# ders1.net
KiCad netlist of a schematic drawn in EAGLE
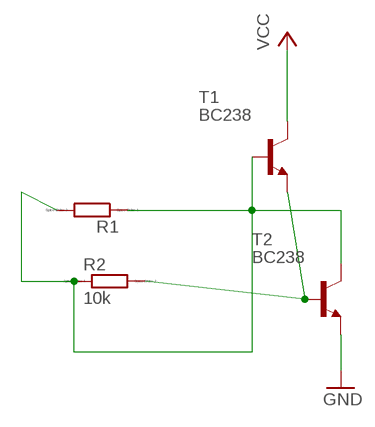
[diagram p0: schematic, sheet 1]

(export (version "E")
  (design (tool "Eeschema 10.0.6"))
  (components
    (comp (ref "R1") (value "R") (footprint "eagle-import:R0805") (libsource (lib "eagle-import") (part "R")))
    (comp (ref "R2")
      (value "10k")
      (footprint "eagle-import:R0805")
      (libsource (lib "eagle-import") (part "R"))
    )
    (comp (ref "T1")
      (value "BC238")
      (footprint "eagle-import:TO92")
      (libsource (lib "eagle-import") (part "BC238"))
    )
    (comp (ref "T2")
      (value "BC238")
      (footprint "eagle-import:TO92")
      (libsource (lib "eagle-import") (part "BC238"))
    )
  )
  (nets
    (net (code "1") (name "GND") (class "Default")
      (node (ref "T2") (pin "1") (pinfunction "E_1") (pintype "passive"))
    )
    (net (code "2") (name "Net-(T1-B)") (class "Default")
      (node (ref "R1") (pin "1") (pinfunction "1_1") (pintype "passive"))
      (node (ref "R1") (pin "2") (pinfunction "2_2") (pintype "passive"))
      (node (ref "R2") (pin "1") (pinfunction "1_1") (pintype "passive"))
      (node (ref "T1") (pin "2") (pinfunction "B_2") (pintype "passive"))
      (node (ref "T2") (pin "3") (pinfunction "C_3") (pintype "passive"))
    )
    (net (code "3") (name "Net-(T1-E)") (class "Default")
      (node (ref "R2") (pin "2") (pinfunction "2_2") (pintype "passive"))
      (node (ref "T1") (pin "1") (pinfunction "E_1") (pintype "passive"))
      (node (ref "T2") (pin "2") (pinfunction "B_2") (pintype "passive"))
    )
    (net (code "4") (name "VCC") (class "Default")
      (node (ref "T1") (pin "3") (pinfunction "C_3") (pintype "passive"))
    )
  )
)
